# PCB-JOY-4AXIS_v07-18_adaptorHirose.net
KiCad netlist of a schematic drawn in EAGLE
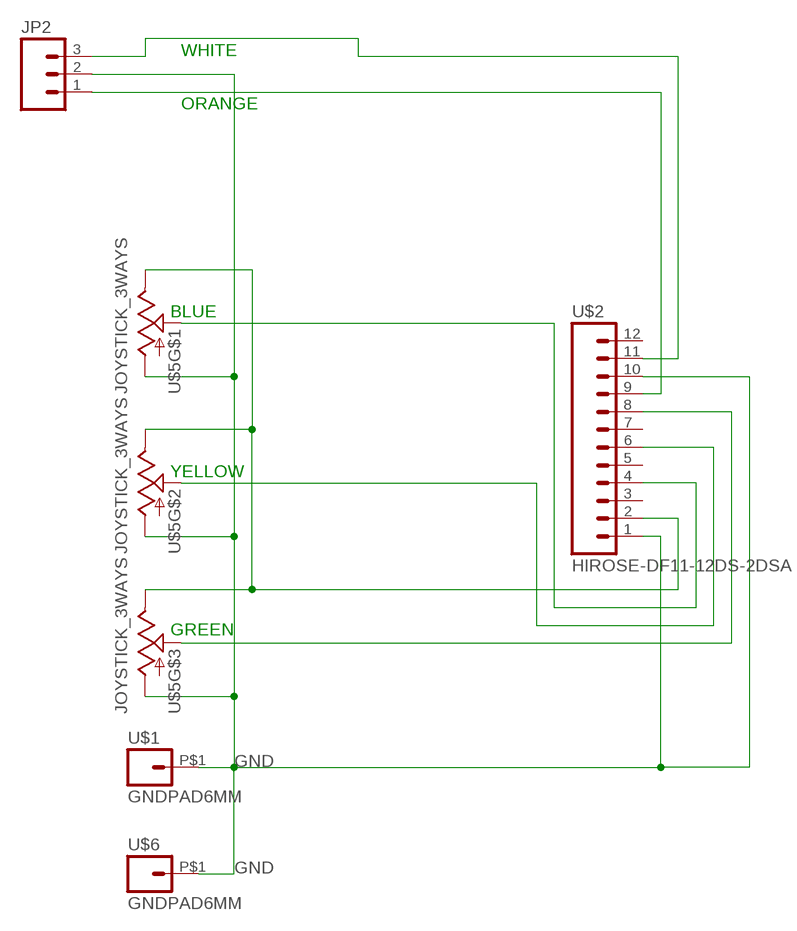
[diagram p0: schematic, sheet 1]

(export (version "E")
  (design (tool "Eeschema 10.0.6"))
  (components
    (comp (ref "JP2")
      (value "M03PTH")
      (footprint "eagle-import:1X03")
      (libsource (lib "eagle-import") (part "M03PTH"))
    )
    (comp (ref "U$1")
      (value "GNDPAD6MM")
      (footprint "eagle-import:3.2MMPAD6MM")
      (libsource (lib "eagle-import") (part "GNDPAD6MM"))
    )
    (comp (ref "U$2")
      (value "HIROSE-DF11-12DS-2DSA")
      (footprint "eagle-import:2X6HIROSE_DF11-12DS-2DSA")
      (libsource (lib "eagle-import") (part "HIROSE-DF11-12DS-2DSA"))
    )
    (comp (ref "U$5")
      (value "JOYSTICK_3WAYS")
      (footprint "eagle-import:JOYSTICK")
      (libsource (lib "eagle-import") (part "JOYSTICK_3WAYS"))
    )
    (comp (ref "U$6")
      (value "GNDPAD6MM")
      (footprint "eagle-import:3.2MMPAD6MM")
      (libsource (lib "eagle-import") (part "GNDPAD6MM"))
    )
  )
  (nets
    (net (code "1") (name "/GND") (class "Default")
      (node (ref "JP2") (pin "2") (pinfunction "2_2") (pintype "passive"))
      (node (ref "U$1") (pin "P$1") (pinfunction "1_P$1") (pintype "passive"))
      (node (ref "U$2") (pin "1") (pinfunction "1_1") (pintype "passive"))
      (node (ref "U$2") (pin "10") (pinfunction "10_10") (pintype "passive"))
      (node (ref "U$5") (pin "LR_COM") (pinfunction "A_LR_COM") (pintype "passive"))
      (node (ref "U$5") (pin "ROT_COM") (pinfunction "A_ROT_COM") (pintype "passive"))
      (node (ref "U$5") (pin "UD_COM") (pinfunction "A_UD_COM") (pintype "passive"))
      (node (ref "U$6") (pin "P$1") (pinfunction "1_P$1") (pintype "passive"))
    )
    (net (code "2") (name "Net-(JP2-Pad1)") (class "Default")
      (node (ref "JP2") (pin "1") (pinfunction "1_1") (pintype "passive"))
      (node (ref "U$2") (pin "9") (pinfunction "9_9") (pintype "passive"))
    )
    (net (code "3") (name "Net-(JP2-Pad3)") (class "Default")
      (node (ref "JP2") (pin "3") (pinfunction "3_3") (pintype "passive"))
      (node (ref "U$2") (pin "11") (pinfunction "11_11") (pintype "passive"))
    )
    (net (code "4") (name "Net-(U$5A-E)") (class "Default")
      (node (ref "U$2") (pin "2") (pinfunction "2_2") (pintype "passive"))
      (node (ref "U$5") (pin "LR_V") (pinfunction "E_LR_V") (pintype "passive"))
      (node (ref "U$5") (pin "ROT_V") (pinfunction "E_ROT_V") (pintype "passive"))
      (node (ref "U$5") (pin "UD_V") (pinfunction "E_UD_V") (pintype "passive"))
    )
    (net (code "5") (name "Net-(U$5A-S)") (class "Default")
      (node (ref "U$2") (pin "4") (pinfunction "4_4") (pintype "passive"))
      (node (ref "U$5") (pin "LR_C") (pinfunction "S_LR_C") (pintype "passive"))
    )
    (net (code "6") (name "Net-(U$5B-S)") (class "Default")
      (node (ref "U$2") (pin "6") (pinfunction "6_6") (pintype "passive"))
      (node (ref "U$5") (pin "UD_C") (pinfunction "S_UD_C") (pintype "passive"))
    )
    (net (code "7") (name "Net-(U$5C-S)") (class "Default")
      (node (ref "U$2") (pin "8") (pinfunction "8_8") (pintype "passive"))
      (node (ref "U$5") (pin "ROT_C") (pinfunction "S_ROT_C") (pintype "passive"))
    )
    (net (code "8") (name "unconnected-(U$2-Pad3)") (class "Default")
      (node (ref "U$2") (pin "3") (pinfunction "3_3") (pintype "passive"))
    )
    (net (code "9") (name "unconnected-(U$2-Pad5)") (class "Default")
      (node (ref "U$2") (pin "5") (pinfunction "5_5") (pintype "passive"))
    )
    (net (code "10") (name "unconnected-(U$2-Pad7)") (class "Default")
      (node (ref "U$2") (pin "7") (pinfunction "7_7") (pintype "passive"))
    )
    (net (code "11") (name "unconnected-(U$2-Pad12)") (class "Default")
      (node (ref "U$2") (pin "12") (pinfunction "12_12") (pintype "passive"))
    )
  )
)
